# i2c-sensor-bridge.net
KiCad netlist of a schematic drawn in EAGLE
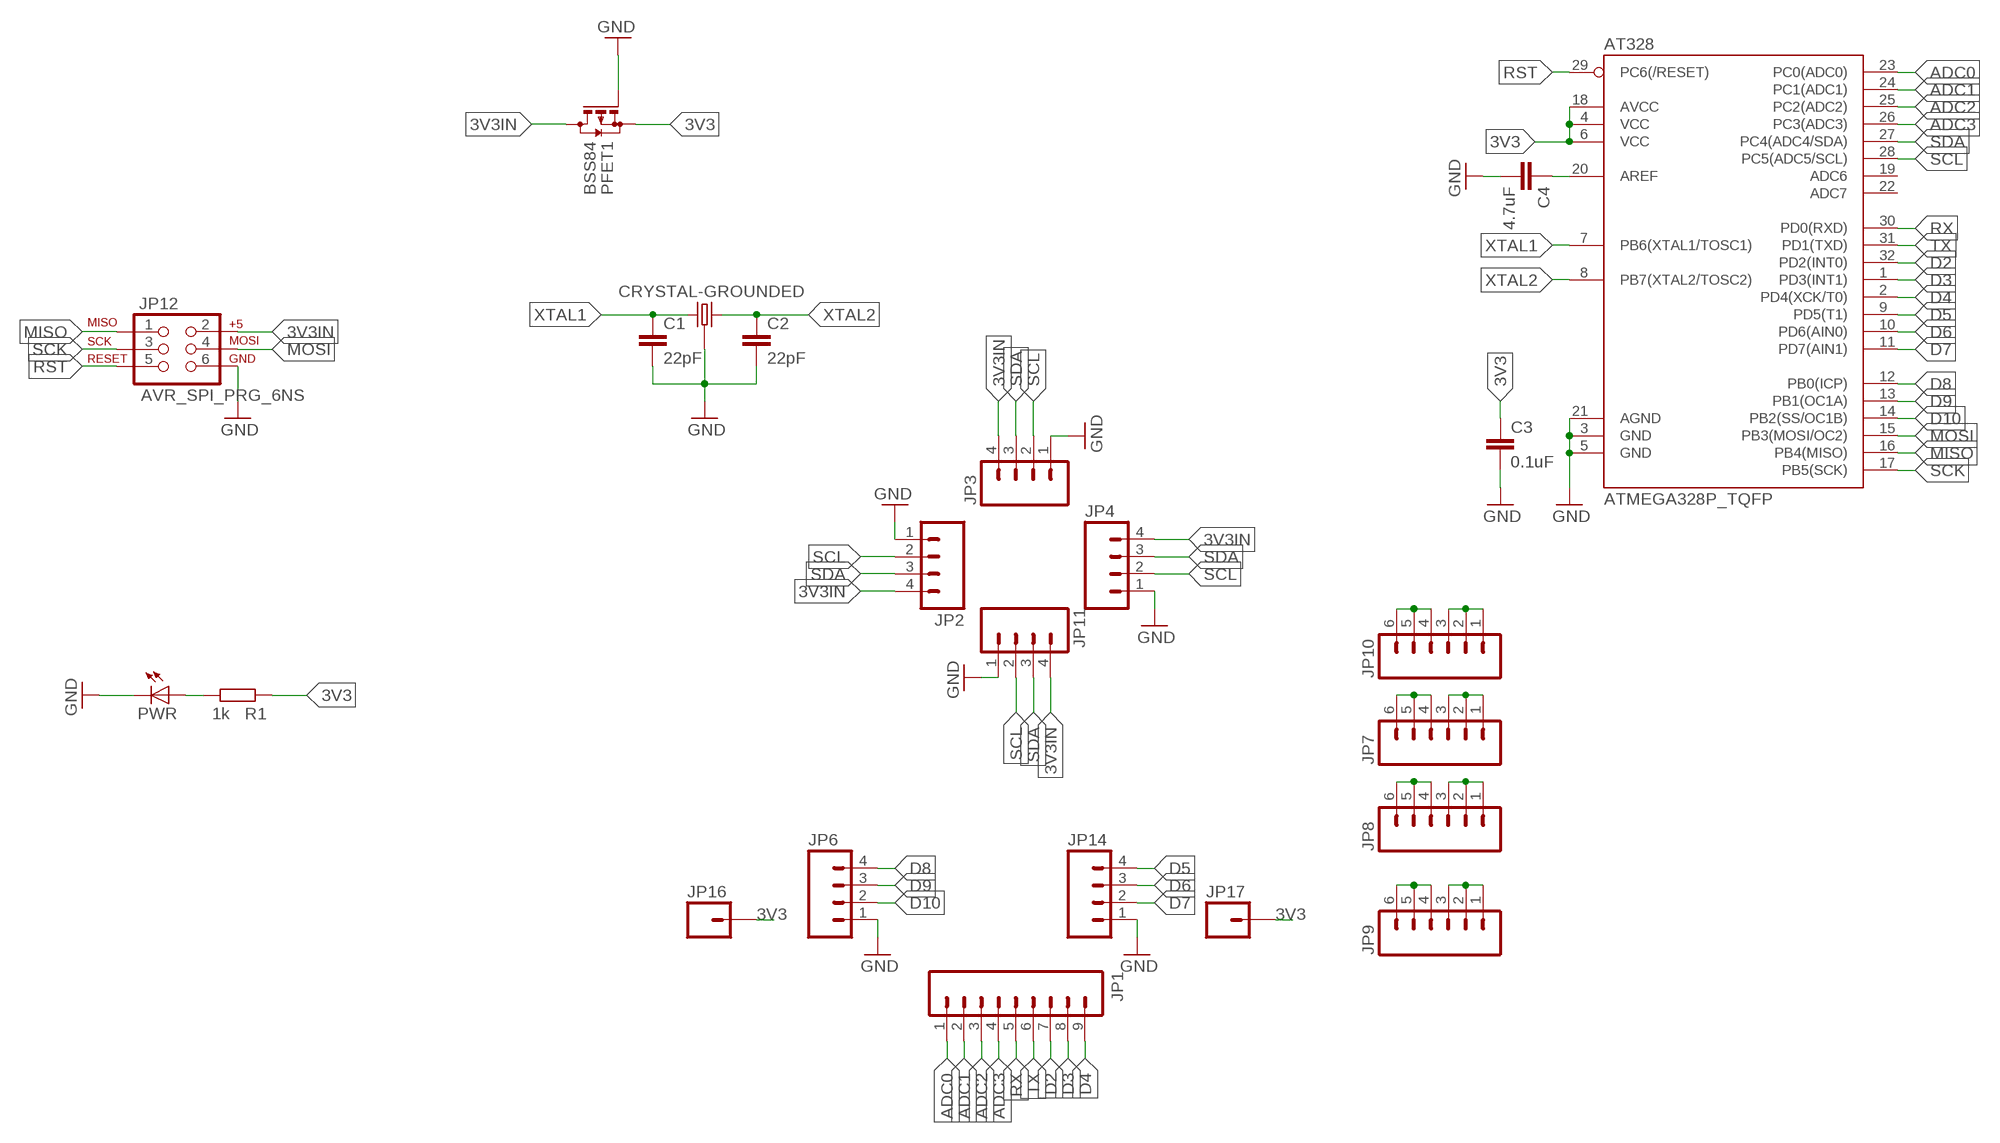
[diagram p0: schematic, sheet 1]

(export (version "E")
  (design (tool "Eeschema 10.0.6"))
  (components
    (comp (ref "AT328")
      (value "ATMEGA328P_TQFP")
      (footprint "eagle-import:TQFP32-08")
      (libsource (lib "eagle-import") (part "ATMEGA328P_TQFP"))
    )
    (comp (ref "C1")
      (value "22pF")
      (footprint "eagle-import:C0805")
      (libsource (lib "eagle-import") (part "C-EUC0805"))
    )
    (comp (ref "C2")
      (value "22pF")
      (footprint "eagle-import:C0805")
      (libsource (lib "eagle-import") (part "C-EUC0805"))
    )
    (comp (ref "C3")
      (value "0.1uF")
      (footprint "eagle-import:C0805")
      (libsource (lib "eagle-import") (part "C-EUC0805"))
    )
    (comp (ref "C4")
      (value "4.7uF")
      (footprint "eagle-import:C0805")
      (libsource (lib "eagle-import") (part "C-EUC0805"))
    )
    (comp (ref "CRYSTAL")
      (value "CRYSTAL-GROUNDED")
      (footprint "eagle-import:CRYSTAL-SMD-5X3")
      (libsource (lib "eagle-import") (part "CRYSTAL-GROUNDED"))
    )
    (comp (ref "JP1")
      (value "M09LOCK")
      (footprint "eagle-import:1X09_LOCK")
      (libsource (lib "eagle-import") (part "M09LOCK"))
    )
    (comp (ref "JP2")
      (value "M04LOCK")
      (footprint "eagle-import:1X04_LOCK")
      (libsource (lib "eagle-import") (part "M04LOCK"))
    )
    (comp (ref "JP3")
      (value "M04LOCK")
      (footprint "eagle-import:1X04_LOCK")
      (libsource (lib "eagle-import") (part "M04LOCK"))
    )
    (comp (ref "JP4")
      (value "M04LOCK")
      (footprint "eagle-import:1X04_LOCK")
      (libsource (lib "eagle-import") (part "M04LOCK"))
    )
    (comp (ref "JP6")
      (value "M04LOCK")
      (footprint "eagle-import:1X04_LOCK")
      (libsource (lib "eagle-import") (part "M04LOCK"))
    )
    (comp (ref "JP7")
      (value "M06NO_SILK_FEMALE_PTH")
      (footprint "eagle-import:1X06_NO_SILK")
      (libsource (lib "eagle-import") (part "M06NO_SILK_FEMALE_PTH"))
    )
    (comp (ref "JP8")
      (value "M06NO_SILK_FEMALE_PTH")
      (footprint "eagle-import:1X06_NO_SILK")
      (libsource (lib "eagle-import") (part "M06NO_SILK_FEMALE_PTH"))
    )
    (comp (ref "JP9")
      (value "M06NO_SILK_FEMALE_PTH")
      (footprint "eagle-import:1X06_NO_SILK")
      (libsource (lib "eagle-import") (part "M06NO_SILK_FEMALE_PTH"))
    )
    (comp (ref "JP10")
      (value "M06NO_SILK_FEMALE_PTH")
      (footprint "eagle-import:1X06_NO_SILK")
      (libsource (lib "eagle-import") (part "M06NO_SILK_FEMALE_PTH"))
    )
    (comp (ref "JP11")
      (value "M04LOCK")
      (footprint "eagle-import:1X04_LOCK")
      (libsource (lib "eagle-import") (part "M04LOCK"))
    )
    (comp (ref "JP12")
      (value "AVR_SPI_PRG_6NS")
      (footprint "eagle-import:2X3-NS")
      (libsource (lib "eagle-import") (part "AVR_SPI_PRG_6NS"))
    )
    (comp (ref "JP14")
      (value "M04LOCK")
      (footprint "eagle-import:1X04_LOCK")
      (libsource (lib "eagle-import") (part "M04LOCK"))
    )
    (comp (ref "JP16")
      (value "M01PTH_NO_SILK_YES_STOP")
      (footprint "eagle-import:1X01_NO_SILK")
      (libsource (lib "eagle-import") (part "M01PTH_NO_SILK_YES_STOP"))
    )
    (comp (ref "JP17")
      (value "M01PTH_NO_SILK_YES_STOP")
      (footprint "eagle-import:1X01_NO_SILK")
      (libsource (lib "eagle-import") (part "M01PTH_NO_SILK_YES_STOP"))
    )
    (comp (ref "PFET1")
      (value "BSS84")
      (footprint "eagle-import:SOT23")
      (libsource (lib "eagle-import") (part "BSS84"))
    )
    (comp (ref "PWR")
      (value "LEDCHIPLED_0805")
      (footprint "eagle-import:CHIPLED_0805")
      (libsource (lib "eagle-import") (part "LEDCHIPLED_0805"))
    )
    (comp (ref "R1")
      (value "1k")
      (footprint "eagle-import:R0805")
      (libsource (lib "eagle-import") (part "R-EU_R0805"))
    )
  )
  (nets
    (net (code "1") (name "3V3") (class "Default")
      (node (ref "AT328") (pin "18") (pinfunction "AVCC_18") (pintype "bidirectional"))
      (node (ref "AT328") (pin "4") (pinfunction "VCC_4") (pintype "bidirectional"))
      (node (ref "AT328") (pin "6") (pinfunction "VCC_6") (pintype "bidirectional"))
      (node (ref "C3") (pin "1") (pinfunction "1_1") (pintype "passive"))
      (node (ref "JP16") (pin "1") (pinfunction "1_1") (pintype "passive"))
      (node (ref "JP17") (pin "1") (pinfunction "1_1") (pintype "passive"))
      (node (ref "PFET1") (pin "2") (pinfunction "S_2") (pintype "passive"))
      (node (ref "R1") (pin "2") (pinfunction "2_2") (pintype "passive"))
    )
    (net (code "2") (name "3V3IN") (class "Default")
      (node (ref "JP11") (pin "4") (pinfunction "4_4") (pintype "passive"))
      (node (ref "JP12") (pin "2") (pinfunction "2_2") (pintype "passive"))
      (node (ref "JP2") (pin "4") (pinfunction "4_4") (pintype "passive"))
      (node (ref "JP3") (pin "4") (pinfunction "4_4") (pintype "passive"))
      (node (ref "JP4") (pin "4") (pinfunction "4_4") (pintype "passive"))
      (node (ref "PFET1") (pin "3") (pinfunction "D_3") (pintype "passive"))
    )
    (net (code "3") (name "ADC0") (class "Default")
      (node (ref "AT328") (pin "23") (pinfunction "PC0(ADC0)_23") (pintype "bidirectional"))
      (node (ref "JP1") (pin "1") (pinfunction "1_1") (pintype "passive"))
    )
    (net (code "4") (name "ADC1") (class "Default")
      (node (ref "AT328") (pin "24") (pinfunction "PC1(ADC1)_24") (pintype "bidirectional"))
      (node (ref "JP1") (pin "2") (pinfunction "2_2") (pintype "passive"))
    )
    (net (code "5") (name "ADC2") (class "Default")
      (node (ref "AT328") (pin "25") (pinfunction "PC2(ADC2)_25") (pintype "bidirectional"))
      (node (ref "JP1") (pin "3") (pinfunction "3_3") (pintype "passive"))
    )
    (net (code "6") (name "ADC3") (class "Default")
      (node (ref "AT328") (pin "26") (pinfunction "PC3(ADC3)_26") (pintype "bidirectional"))
      (node (ref "JP1") (pin "4") (pinfunction "4_4") (pintype "passive"))
    )
    (net (code "7") (name "D2") (class "Default")
      (node (ref "AT328") (pin "32") (pinfunction "PD2(INT0)_32") (pintype "bidirectional"))
      (node (ref "JP1") (pin "7") (pinfunction "7_7") (pintype "passive"))
    )
    (net (code "8") (name "D3") (class "Default")
      (node (ref "AT328") (pin "1") (pinfunction "PD3(INT1)_1") (pintype "bidirectional"))
      (node (ref "JP1") (pin "8") (pinfunction "8_8") (pintype "passive"))
    )
    (net (code "9") (name "D4") (class "Default")
      (node (ref "AT328") (pin "2") (pinfunction "PD4(XCK/T0)_2") (pintype "bidirectional"))
      (node (ref "JP1") (pin "9") (pinfunction "9_9") (pintype "passive"))
    )
    (net (code "10") (name "D5") (class "Default")
      (node (ref "AT328") (pin "9") (pinfunction "PD5(T1)_9") (pintype "bidirectional"))
      (node (ref "JP14") (pin "4") (pinfunction "4_4") (pintype "passive"))
    )
    (net (code "11") (name "D6") (class "Default")
      (node (ref "AT328") (pin "10") (pinfunction "PD6(AIN0)_10") (pintype "bidirectional"))
      (node (ref "JP14") (pin "3") (pinfunction "3_3") (pintype "passive"))
    )
    (net (code "12") (name "D7") (class "Default")
      (node (ref "AT328") (pin "11") (pinfunction "PD7(AIN1)_11") (pintype "bidirectional"))
      (node (ref "JP14") (pin "2") (pinfunction "2_2") (pintype "passive"))
    )
    (net (code "13") (name "D8") (class "Default")
      (node (ref "AT328") (pin "12") (pinfunction "PB0(ICP)_12") (pintype "bidirectional"))
      (node (ref "JP6") (pin "4") (pinfunction "4_4") (pintype "passive"))
    )
    (net (code "14") (name "D9") (class "Default")
      (node (ref "AT328") (pin "13") (pinfunction "PB1(OC1A)_13") (pintype "bidirectional"))
      (node (ref "JP6") (pin "3") (pinfunction "3_3") (pintype "passive"))
    )
    (net (code "15") (name "D10") (class "Default")
      (node (ref "AT328") (pin "14") (pinfunction "PB2(SS/OC1B)_14") (pintype "bidirectional"))
      (node (ref "JP6") (pin "2") (pinfunction "2_2") (pintype "passive"))
    )
    (net (code "16") (name "GND") (class "Default")
      (node (ref "AT328") (pin "21") (pinfunction "AGND_21") (pintype "bidirectional"))
      (node (ref "AT328") (pin "3") (pinfunction "GND_3") (pintype "bidirectional"))
      (node (ref "AT328") (pin "5") (pinfunction "GND_5") (pintype "bidirectional"))
      (node (ref "C1") (pin "2") (pinfunction "2_2") (pintype "passive"))
      (node (ref "C2") (pin "2") (pinfunction "2_2") (pintype "passive"))
      (node (ref "C3") (pin "2") (pinfunction "2_2") (pintype "passive"))
      (node (ref "C4") (pin "2") (pinfunction "2_2") (pintype "passive"))
      (node (ref "CRYSTAL") (pin "2") (pinfunction "3_2") (pintype "passive"))
      (node (ref "CRYSTAL") (pin "4") (pinfunction "3_4") (pintype "passive"))
      (node (ref "JP11") (pin "1") (pinfunction "1_1") (pintype "passive"))
      (node (ref "JP12") (pin "6") (pinfunction "6_6") (pintype "passive"))
      (node (ref "JP14") (pin "1") (pinfunction "1_1") (pintype "passive"))
      (node (ref "JP2") (pin "1") (pinfunction "1_1") (pintype "passive"))
      (node (ref "JP3") (pin "1") (pinfunction "1_1") (pintype "passive"))
      (node (ref "JP4") (pin "1") (pinfunction "1_1") (pintype "passive"))
      (node (ref "JP6") (pin "1") (pinfunction "1_1") (pintype "passive"))
      (node (ref "PFET1") (pin "1") (pinfunction "G_1") (pintype "passive"))
      (node (ref "PWR") (pin "C") (pinfunction "C_C") (pintype "passive"))
    )
    (net (code "17") (name "MISO") (class "Default")
      (node (ref "AT328") (pin "16") (pinfunction "PB4(MISO)_16") (pintype "bidirectional"))
      (node (ref "JP12") (pin "1") (pinfunction "1_1") (pintype "passive"))
    )
    (net (code "18") (name "MOSI") (class "Default")
      (node (ref "AT328") (pin "15") (pinfunction "PB3(MOSI/OC2)_15") (pintype "bidirectional"))
      (node (ref "JP12") (pin "4") (pinfunction "4_4") (pintype "passive"))
    )
    (net (code "19") (name "Net-(AT328-AREF)") (class "Default")
      (node (ref "AT328") (pin "20") (pinfunction "AREF_20") (pintype "bidirectional"))
      (node (ref "C4") (pin "1") (pinfunction "1_1") (pintype "passive"))
    )
    (net (code "20") (name "Net-(JP7-Pad1)") (class "Default")
      (node (ref "JP7") (pin "1") (pinfunction "1_1") (pintype "passive"))
      (node (ref "JP7") (pin "2") (pinfunction "2_2") (pintype "passive"))
      (node (ref "JP7") (pin "3") (pinfunction "3_3") (pintype "passive"))
    )
    (net (code "21") (name "Net-(JP7-Pad4)") (class "Default")
      (node (ref "JP7") (pin "4") (pinfunction "4_4") (pintype "passive"))
      (node (ref "JP7") (pin "5") (pinfunction "5_5") (pintype "passive"))
      (node (ref "JP7") (pin "6") (pinfunction "6_6") (pintype "passive"))
    )
    (net (code "22") (name "Net-(JP8-Pad1)") (class "Default")
      (node (ref "JP8") (pin "1") (pinfunction "1_1") (pintype "passive"))
      (node (ref "JP8") (pin "2") (pinfunction "2_2") (pintype "passive"))
      (node (ref "JP8") (pin "3") (pinfunction "3_3") (pintype "passive"))
    )
    (net (code "23") (name "Net-(JP8-Pad4)") (class "Default")
      (node (ref "JP8") (pin "4") (pinfunction "4_4") (pintype "passive"))
      (node (ref "JP8") (pin "5") (pinfunction "5_5") (pintype "passive"))
      (node (ref "JP8") (pin "6") (pinfunction "6_6") (pintype "passive"))
    )
    (net (code "24") (name "Net-(JP9-Pad1)") (class "Default")
      (node (ref "JP9") (pin "1") (pinfunction "1_1") (pintype "passive"))
      (node (ref "JP9") (pin "2") (pinfunction "2_2") (pintype "passive"))
      (node (ref "JP9") (pin "3") (pinfunction "3_3") (pintype "passive"))
    )
    (net (code "25") (name "Net-(JP9-Pad4)") (class "Default")
      (node (ref "JP9") (pin "4") (pinfunction "4_4") (pintype "passive"))
      (node (ref "JP9") (pin "5") (pinfunction "5_5") (pintype "passive"))
      (node (ref "JP9") (pin "6") (pinfunction "6_6") (pintype "passive"))
    )
    (net (code "26") (name "Net-(JP10-Pad1)") (class "Default")
      (node (ref "JP10") (pin "1") (pinfunction "1_1") (pintype "passive"))
      (node (ref "JP10") (pin "2") (pinfunction "2_2") (pintype "passive"))
      (node (ref "JP10") (pin "3") (pinfunction "3_3") (pintype "passive"))
    )
    (net (code "27") (name "Net-(JP10-Pad4)") (class "Default")
      (node (ref "JP10") (pin "4") (pinfunction "4_4") (pintype "passive"))
      (node (ref "JP10") (pin "5") (pinfunction "5_5") (pintype "passive"))
      (node (ref "JP10") (pin "6") (pinfunction "6_6") (pintype "passive"))
    )
    (net (code "28") (name "Net-(PWR-PadA)") (class "Default")
      (node (ref "PWR") (pin "A") (pinfunction "A_A") (pintype "passive"))
      (node (ref "R1") (pin "1") (pinfunction "1_1") (pintype "passive"))
    )
    (net (code "29") (name "RST") (class "Default")
      (node (ref "AT328") (pin "29") (pinfunction "PC6(/RESET)_29") (pintype "bidirectional"))
      (node (ref "JP12") (pin "5") (pinfunction "5_5") (pintype "passive"))
    )
    (net (code "30") (name "RX") (class "Default")
      (node (ref "AT328") (pin "30") (pinfunction "PD0(RXD)_30") (pintype "bidirectional"))
      (node (ref "JP1") (pin "5") (pinfunction "5_5") (pintype "passive"))
    )
    (net (code "31") (name "SCK") (class "Default")
      (node (ref "AT328") (pin "17") (pinfunction "PB5(SCK)_17") (pintype "bidirectional"))
      (node (ref "JP12") (pin "3") (pinfunction "3_3") (pintype "passive"))
    )
    (net (code "32") (name "SCL") (class "Default")
      (node (ref "AT328") (pin "28") (pinfunction "PC5(ADC5/SCL)_28") (pintype "bidirectional"))
      (node (ref "JP11") (pin "2") (pinfunction "2_2") (pintype "passive"))
      (node (ref "JP2") (pin "2") (pinfunction "2_2") (pintype "passive"))
      (node (ref "JP3") (pin "2") (pinfunction "2_2") (pintype "passive"))
      (node (ref "JP4") (pin "2") (pinfunction "2_2") (pintype "passive"))
    )
    (net (code "33") (name "SDA") (class "Default")
      (node (ref "AT328") (pin "27") (pinfunction "PC4(ADC4/SDA)_27") (pintype "bidirectional"))
      (node (ref "JP11") (pin "3") (pinfunction "3_3") (pintype "passive"))
      (node (ref "JP2") (pin "3") (pinfunction "3_3") (pintype "passive"))
      (node (ref "JP3") (pin "3") (pinfunction "3_3") (pintype "passive"))
      (node (ref "JP4") (pin "3") (pinfunction "3_3") (pintype "passive"))
    )
    (net (code "34") (name "TX") (class "Default")
      (node (ref "AT328") (pin "31") (pinfunction "PD1(TXD)_31") (pintype "bidirectional"))
      (node (ref "JP1") (pin "6") (pinfunction "6_6") (pintype "passive"))
    )
    (net (code "35") (name "XTAL1") (class "Default")
      (node (ref "AT328") (pin "7") (pinfunction "PB6(XTAL1/TOSC1)_7") (pintype "bidirectional"))
      (node (ref "C1") (pin "1") (pinfunction "1_1") (pintype "passive"))
      (node (ref "CRYSTAL") (pin "3") (pinfunction "1_3") (pintype "passive"))
    )
    (net (code "36") (name "XTAL2") (class "Default")
      (node (ref "AT328") (pin "8") (pinfunction "PB7(XTAL2/TOSC2)_8") (pintype "bidirectional"))
      (node (ref "C2") (pin "1") (pinfunction "1_1") (pintype "passive"))
      (node (ref "CRYSTAL") (pin "1") (pinfunction "2_1") (pintype "passive"))
    )
    (net (code "37") (name "unconnected-(AT328-ADC6-Pad19)") (class "Default")
      (node (ref "AT328") (pin "19") (pinfunction "ADC6_19") (pintype "bidirectional"))
    )
    (net (code "38") (name "unconnected-(AT328-ADC7-Pad22)") (class "Default")
      (node (ref "AT328") (pin "22") (pinfunction "ADC7_22") (pintype "bidirectional"))
    )
  )
)
